# Memory.net
KiCad netlist of a schematic drawn in Altium Designer
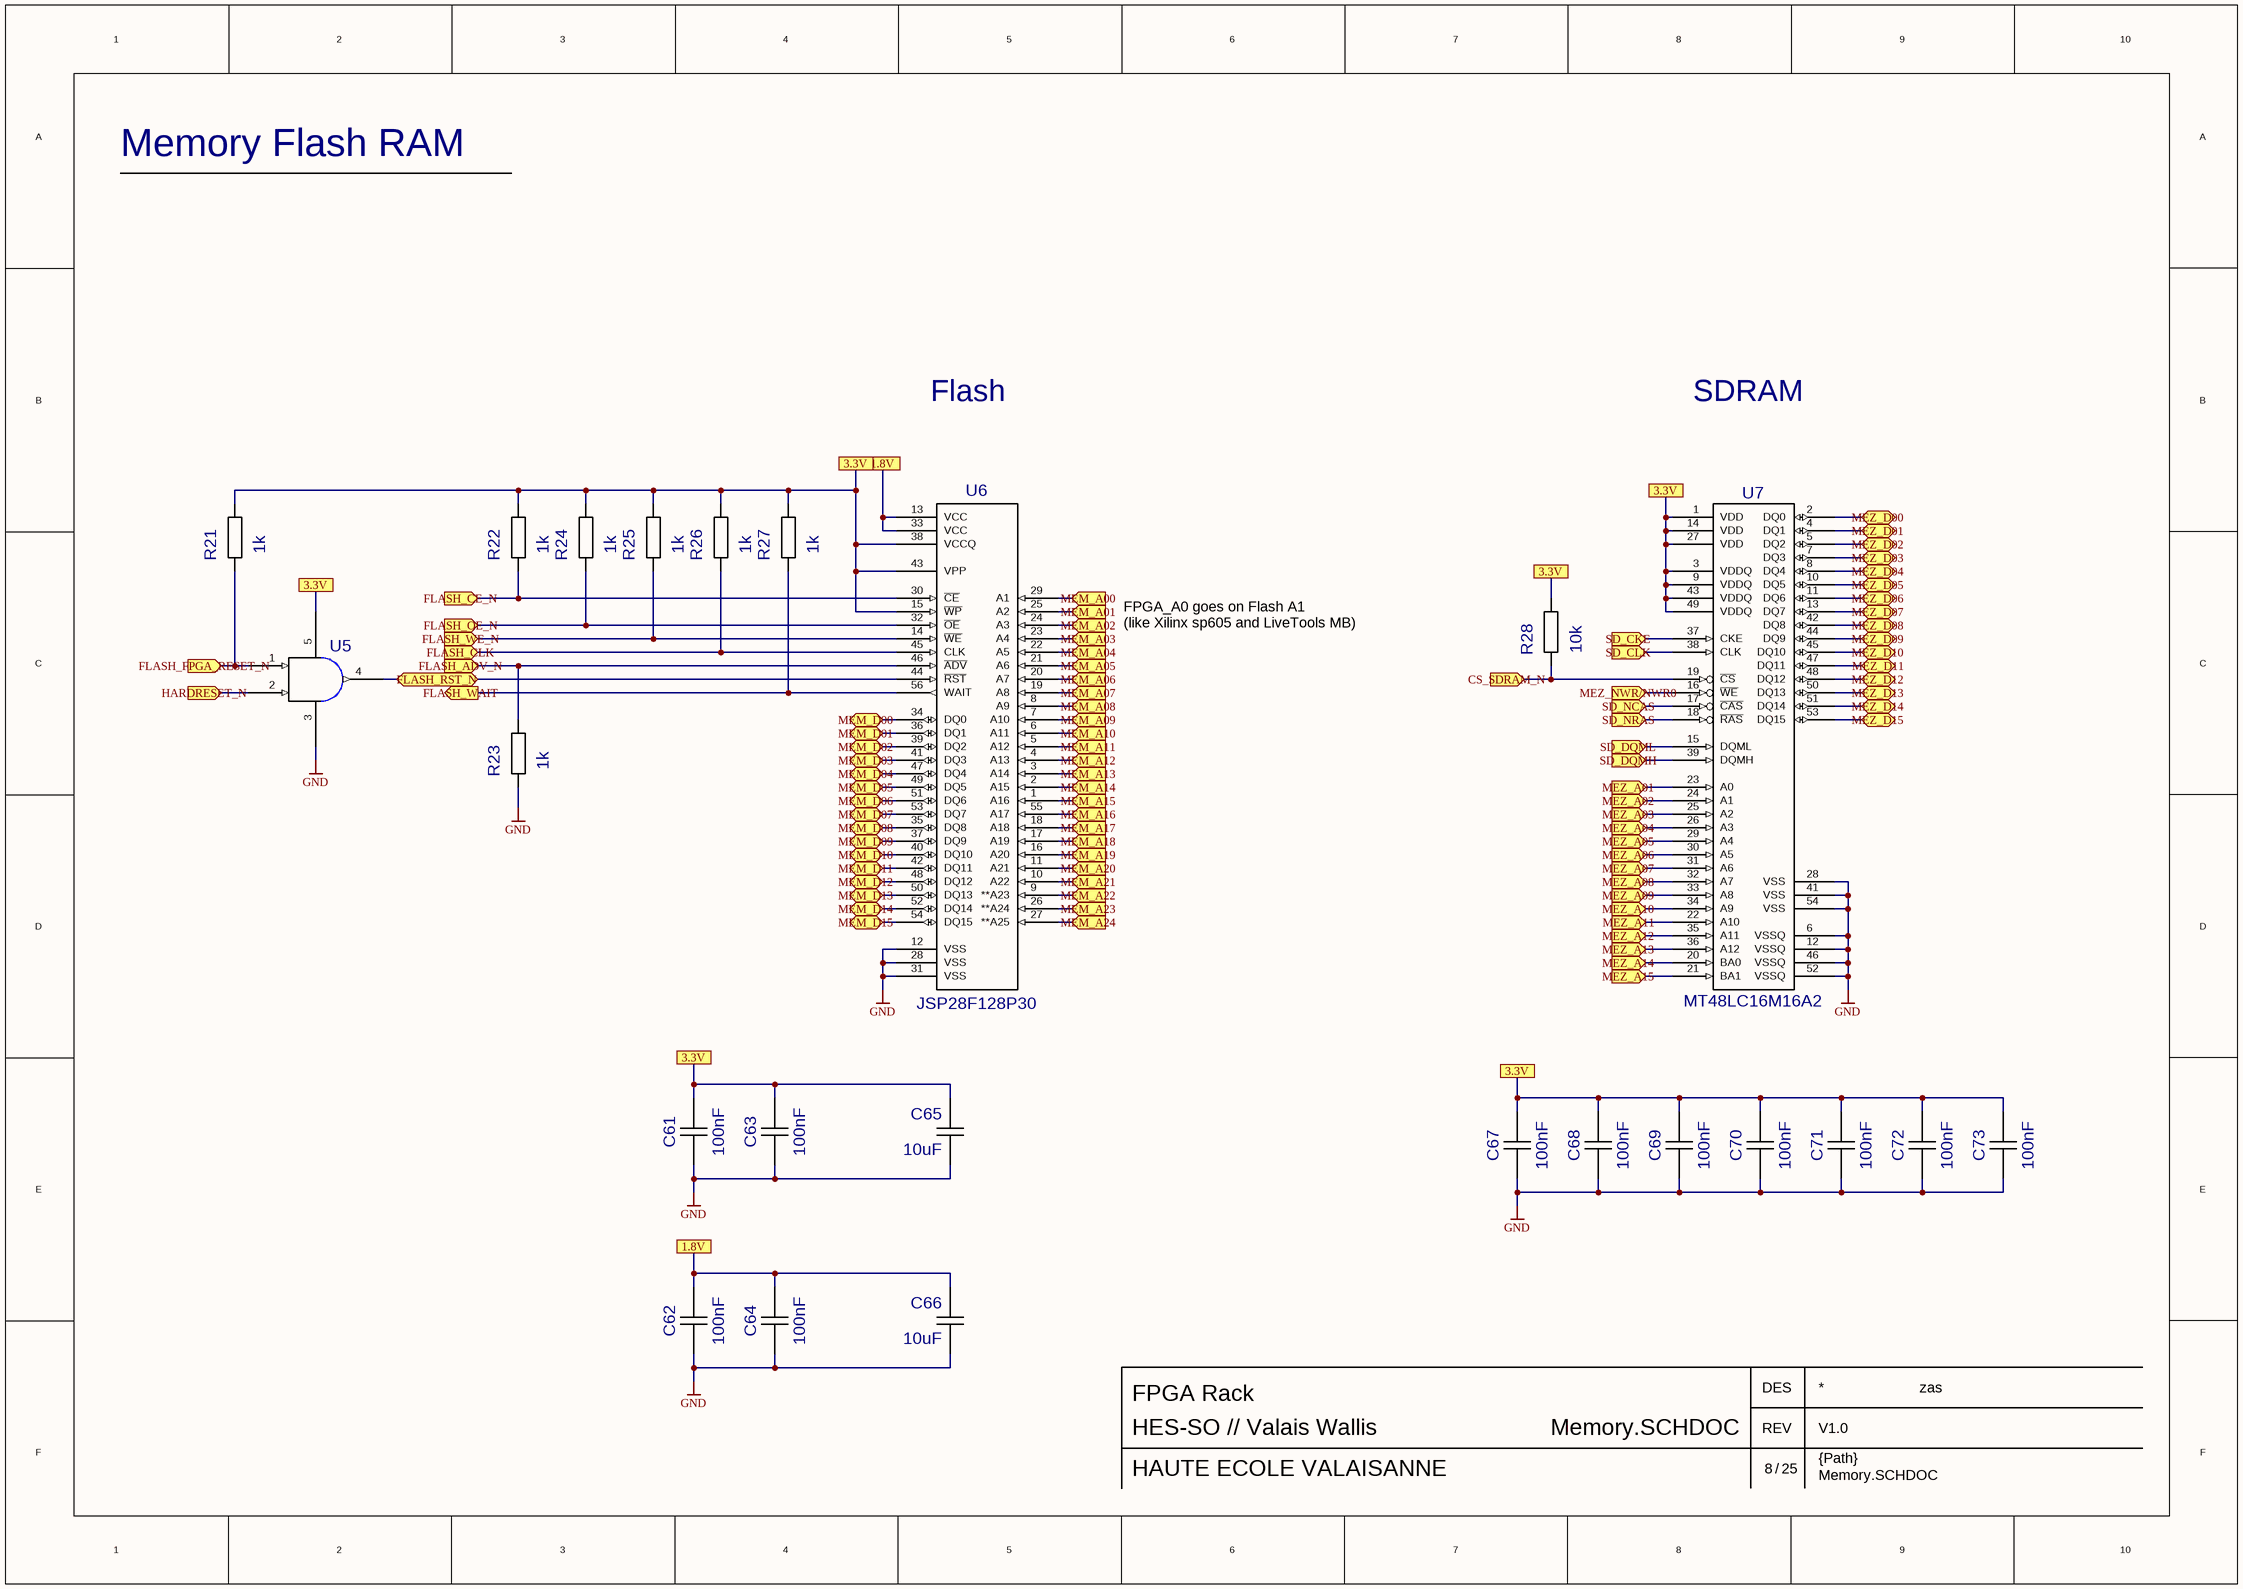
[diagram p0: Memory.SCHDOC]

(export (version "E")
  (design (tool "Eeschema 10.0.6"))
  (components
    (comp (ref "C61")
      (value "100nF")
      (footprint "CC0805-MM")
      (description "Capacitor")
      (fields (field (name "Comment") "CAPS0805-MM"))
      (libsource (lib "*") (part "CAPS0805-MM"))
    )
    (comp (ref "C62")
      (value "100nF")
      (footprint "CC0805-MM")
      (description "Capacitor")
      (fields (field (name "Comment") "CAPS0805-MM"))
      (libsource (lib "*") (part "CAPS0805-MM"))
    )
    (comp (ref "C63")
      (value "100nF")
      (footprint "CC0805-MM")
      (description "Capacitor")
      (fields (field (name "Comment") "CAPS0805-MM"))
      (libsource (lib "*") (part "CAPS0805-MM"))
    )
    (comp (ref "C64")
      (value "100nF")
      (footprint "CC0805-MM")
      (description "Capacitor")
      (fields (field (name "Comment") "CAPS0805-MM"))
      (libsource (lib "*") (part "CAPS0805-MM"))
    )
    (comp (ref "C65")
      (value "10uF")
      (footprint "CC0805-MM")
      (description "Capacitor")
      (fields (field (name "Comment") "CAPS0805-MM"))
      (libsource (lib "*") (part "CAPS0805-MM"))
    )
    (comp (ref "C66")
      (value "10uF")
      (footprint "CC0805-MM")
      (description "Capacitor")
      (fields (field (name "Comment") "CAPS0805-MM"))
      (libsource (lib "*") (part "CAPS0805-MM"))
    )
    (comp (ref "C67")
      (value "100nF")
      (footprint "CC0805-MM")
      (description "Capacitor")
      (fields (field (name "Comment") "CAPS0805-MM"))
      (libsource (lib "*") (part "CAPS0805-MM"))
    )
    (comp (ref "C68")
      (value "100nF")
      (footprint "CC0805-MM")
      (description "Capacitor")
      (fields (field (name "Comment") "CAPS0805-MM"))
      (libsource (lib "*") (part "CAPS0805-MM"))
    )
    (comp (ref "C69")
      (value "100nF")
      (footprint "CC0805-MM")
      (description "Capacitor")
      (fields (field (name "Comment") "CAPS0805-MM"))
      (libsource (lib "*") (part "CAPS0805-MM"))
    )
    (comp (ref "C70")
      (value "100nF")
      (footprint "CC0805-MM")
      (description "Capacitor")
      (fields (field (name "Comment") "CAPS0805-MM"))
      (libsource (lib "*") (part "CAPS0805-MM"))
    )
    (comp (ref "C71")
      (value "100nF")
      (footprint "CC0805-MM")
      (description "Capacitor")
      (fields (field (name "Comment") "CAPS0805-MM"))
      (libsource (lib "*") (part "CAPS0805-MM"))
    )
    (comp (ref "C72")
      (value "100nF")
      (footprint "CC0805-MM")
      (description "Capacitor")
      (fields (field (name "Comment") "CAPS0805-MM"))
      (libsource (lib "*") (part "CAPS0805-MM"))
    )
    (comp (ref "C73")
      (value "100nF")
      (footprint "CC0805-MM")
      (description "Capacitor")
      (fields (field (name "Comment") "CAPS0805-MM"))
      (libsource (lib "*") (part "CAPS0805-MM"))
    )
    (comp (ref "R21")
      (value "1k")
      (footprint "RC0805-MM")
      (description "RS0805-MM")
      (libsource (lib "*") (part "RS0805-MM"))
    )
    (comp (ref "R22")
      (value "1k")
      (footprint "RC0805-MM")
      (description "RS0805-MM")
      (libsource (lib "*") (part "RS0805-MM"))
    )
    (comp (ref "R23")
      (value "1k")
      (footprint "RC0805-MM")
      (description "RS0805-MM")
      (libsource (lib "*") (part "RS0805-MM"))
    )
    (comp (ref "R24")
      (value "1k")
      (footprint "RC0805-MM")
      (description "RS0805-MM")
      (libsource (lib "*") (part "RS0805-MM"))
    )
    (comp (ref "R25")
      (value "1k")
      (footprint "RC0805-MM")
      (description "RS0805-MM")
      (libsource (lib "*") (part "RS0805-MM"))
    )
    (comp (ref "R26")
      (value "1k")
      (footprint "RC0805-MM")
      (description "RS0805-MM")
      (libsource (lib "*") (part "RS0805-MM"))
    )
    (comp (ref "R27")
      (value "1k")
      (footprint "RC0805-MM")
      (description "RS0805-MM")
      (libsource (lib "*") (part "RS0805-MM"))
    )
    (comp (ref "R28")
      (value "10k")
      (footprint "RC0805-MM")
      (description "RS0805-MM")
      (libsource (lib "*") (part "RS0805-MM"))
    )
    (comp (ref "U5")
      (value "NC7SZ08P5")
      (footprint "SC70-5")
      (description "HS Inverter - Fairchild")
      (libsource (lib "*") (part "NC7SZ08P5"))
    )
    (comp (ref "U6")
      (value "JSP28F128P30")
      (footprint "TSOP56")
      (description "SDRAM 64Mb x 16 - Micron")
      (fields (field (name "Comment") "JS28F512P30"))
      (libsource (lib "*") (part "JS28F512P30"))
    )
    (comp (ref "U7")
      (value "MT48LC16M16A2")
      (footprint "TSOP54")
      (description "SDRAM 64Mb x 16 - Micron")
      (libsource (lib "*") (part "MT48LC16M16A2"))
    )
  )
  (nets
    (net (code "3") (name "/CS_SDRAM_N") (class "Default")
      (node (ref "R28") (pin "1") (pinfunction "1_1") (pintype "passive"))
      (node (ref "U7") (pin "19") (pinfunction "~{CS}_19") (pintype "input"))
    )
    (net (code "4") (name "/FLASH_ADV_N") (class "Default")
      (node (ref "R23") (pin "2") (pinfunction "2_2") (pintype "passive"))
      (node (ref "U6") (pin "46") (pinfunction "~{ADV}_46") (pintype "input"))
    )
    (net (code "5") (name "/FLASH_CE_N") (class "Default")
      (node (ref "R22") (pin "1") (pinfunction "1_1") (pintype "passive"))
      (node (ref "U6") (pin "30") (pinfunction "~{CE}_30") (pintype "input"))
    )
    (net (code "6") (name "/FLASH_CLK") (class "Default")
      (node (ref "R26") (pin "1") (pinfunction "1_1") (pintype "passive"))
      (node (ref "U6") (pin "45") (pinfunction "CLK_45") (pintype "input"))
    )
    (net (code "7") (name "/FLASH_FPGA_RESET_N") (class "Default")
      (node (ref "R21") (pin "1") (pinfunction "1_1") (pintype "passive"))
      (node (ref "U5") (pin "1") (pinfunction "A_1") (pintype "input"))
    )
    (net (code "8") (name "/FLASH_OE_N") (class "Default")
      (node (ref "R24") (pin "1") (pinfunction "1_1") (pintype "passive"))
      (node (ref "U6") (pin "32") (pinfunction "~{OE}_32") (pintype "input"))
    )
    (net (code "9") (name "/FLASH_RST_N") (class "Default")
      (node (ref "U5") (pin "4") (pinfunction "Y_4") (pintype "output"))
      (node (ref "U6") (pin "44") (pinfunction "~{RST}_44") (pintype "input"))
    )
    (net (code "10") (name "/FLASH_WAIT") (class "Default")
      (node (ref "R27") (pin "1") (pinfunction "1_1") (pintype "passive"))
      (node (ref "U6") (pin "56") (pinfunction "WAIT_56") (pintype "output"))
    )
    (net (code "11") (name "/FLASH_WE_N") (class "Default")
      (node (ref "R25") (pin "1") (pinfunction "1_1") (pintype "passive"))
      (node (ref "U6") (pin "14") (pinfunction "~{WE}_14") (pintype "input"))
    )
    (net (code "12") (name "/HARDRESET_N") (class "Default")
      (node (ref "U5") (pin "2") (pinfunction "B_2") (pintype "input"))
    )
    (net (code "13") (name "/MEM_A00") (class "Default")
      (node (ref "U6") (pin "29") (pinfunction "A1_29") (pintype "input"))
    )
    (net (code "14") (name "/MEM_A01") (class "Default")
      (node (ref "U6") (pin "25") (pinfunction "A2_25") (pintype "input"))
    )
    (net (code "15") (name "/MEM_A02") (class "Default")
      (node (ref "U6") (pin "24") (pinfunction "A3_24") (pintype "input"))
    )
    (net (code "16") (name "/MEM_A03") (class "Default")
      (node (ref "U6") (pin "23") (pinfunction "A4_23") (pintype "input"))
    )
    (net (code "17") (name "/MEM_A04") (class "Default")
      (node (ref "U6") (pin "22") (pinfunction "A5_22") (pintype "input"))
    )
    (net (code "18") (name "/MEM_A05") (class "Default")
      (node (ref "U6") (pin "21") (pinfunction "A6_21") (pintype "input"))
    )
    (net (code "19") (name "/MEM_A06") (class "Default")
      (node (ref "U6") (pin "20") (pinfunction "A7_20") (pintype "input"))
    )
    (net (code "20") (name "/MEM_A07") (class "Default")
      (node (ref "U6") (pin "19") (pinfunction "A8_19") (pintype "input"))
    )
    (net (code "21") (name "/MEM_A08") (class "Default")
      (node (ref "U6") (pin "8") (pinfunction "A9_8") (pintype "input"))
    )
    (net (code "22") (name "/MEM_A09") (class "Default")
      (node (ref "U6") (pin "7") (pinfunction "A10_7") (pintype "input"))
    )
    (net (code "23") (name "/MEM_A10") (class "Default")
      (node (ref "U6") (pin "6") (pinfunction "A11_6") (pintype "input"))
    )
    (net (code "24") (name "/MEM_A11") (class "Default")
      (node (ref "U6") (pin "5") (pinfunction "A12_5") (pintype "input"))
    )
    (net (code "25") (name "/MEM_A12") (class "Default")
      (node (ref "U6") (pin "4") (pinfunction "A13_4") (pintype "input"))
    )
    (net (code "26") (name "/MEM_A13") (class "Default")
      (node (ref "U6") (pin "3") (pinfunction "A14_3") (pintype "input"))
    )
    (net (code "27") (name "/MEM_A14") (class "Default")
      (node (ref "U6") (pin "2") (pinfunction "A15_2") (pintype "input"))
    )
    (net (code "28") (name "/MEM_A15") (class "Default")
      (node (ref "U6") (pin "1") (pinfunction "A16_1") (pintype "input"))
    )
    (net (code "29") (name "/MEM_A16") (class "Default")
      (node (ref "U6") (pin "55") (pinfunction "A17_55") (pintype "input"))
    )
    (net (code "30") (name "/MEM_A17") (class "Default")
      (node (ref "U6") (pin "18") (pinfunction "A18_18") (pintype "input"))
    )
    (net (code "31") (name "/MEM_A18") (class "Default")
      (node (ref "U6") (pin "17") (pinfunction "A19_17") (pintype "input"))
    )
    (net (code "32") (name "/MEM_A19") (class "Default")
      (node (ref "U6") (pin "16") (pinfunction "A20_16") (pintype "input"))
    )
    (net (code "33") (name "/MEM_A20") (class "Default")
      (node (ref "U6") (pin "11") (pinfunction "A21_11") (pintype "input"))
    )
    (net (code "34") (name "/MEM_A21") (class "Default")
      (node (ref "U6") (pin "10") (pinfunction "A22_10") (pintype "input"))
    )
    (net (code "35") (name "/MEM_A22") (class "Default")
      (node (ref "U6") (pin "9") (pinfunction "**A23_9") (pintype "input"))
    )
    (net (code "36") (name "/MEM_A23") (class "Default")
      (node (ref "U6") (pin "26") (pinfunction "**A24_26") (pintype "input"))
    )
    (net (code "37") (name "/MEM_A24") (class "Default")
      (node (ref "U6") (pin "27") (pinfunction "**A25_27") (pintype "input"))
    )
    (net (code "38") (name "/MEM_D00") (class "Default")
      (node (ref "U6") (pin "34") (pinfunction "DQ0_34") (pintype "bidirectional"))
    )
    (net (code "39") (name "/MEM_D01") (class "Default")
      (node (ref "U6") (pin "36") (pinfunction "DQ1_36") (pintype "bidirectional"))
    )
    (net (code "40") (name "/MEM_D02") (class "Default")
      (node (ref "U6") (pin "39") (pinfunction "DQ2_39") (pintype "bidirectional"))
    )
    (net (code "41") (name "/MEM_D03") (class "Default")
      (node (ref "U6") (pin "41") (pinfunction "DQ3_41") (pintype "bidirectional"))
    )
    (net (code "42") (name "/MEM_D04") (class "Default")
      (node (ref "U6") (pin "47") (pinfunction "DQ4_47") (pintype "bidirectional"))
    )
    (net (code "43") (name "/MEM_D05") (class "Default")
      (node (ref "U6") (pin "49") (pinfunction "DQ5_49") (pintype "bidirectional"))
    )
    (net (code "44") (name "/MEM_D06") (class "Default")
      (node (ref "U6") (pin "51") (pinfunction "DQ6_51") (pintype "bidirectional"))
    )
    (net (code "45") (name "/MEM_D07") (class "Default")
      (node (ref "U6") (pin "53") (pinfunction "DQ7_53") (pintype "bidirectional"))
    )
    (net (code "46") (name "/MEM_D08") (class "Default")
      (node (ref "U6") (pin "35") (pinfunction "DQ8_35") (pintype "bidirectional"))
    )
    (net (code "47") (name "/MEM_D09") (class "Default")
      (node (ref "U6") (pin "37") (pinfunction "DQ9_37") (pintype "bidirectional"))
    )
    (net (code "48") (name "/MEM_D10") (class "Default")
      (node (ref "U6") (pin "40") (pinfunction "DQ10_40") (pintype "bidirectional"))
    )
    (net (code "49") (name "/MEM_D11") (class "Default")
      (node (ref "U6") (pin "42") (pinfunction "DQ11_42") (pintype "bidirectional"))
    )
    (net (code "50") (name "/MEM_D12") (class "Default")
      (node (ref "U6") (pin "48") (pinfunction "DQ12_48") (pintype "bidirectional"))
    )
    (net (code "51") (name "/MEM_D13") (class "Default")
      (node (ref "U6") (pin "50") (pinfunction "DQ13_50") (pintype "bidirectional"))
    )
    (net (code "52") (name "/MEM_D14") (class "Default")
      (node (ref "U6") (pin "52") (pinfunction "DQ14_52") (pintype "bidirectional"))
    )
    (net (code "53") (name "/MEM_D15") (class "Default")
      (node (ref "U6") (pin "54") (pinfunction "DQ15_54") (pintype "bidirectional"))
    )
    (net (code "54") (name "/MEZ_A01") (class "Default")
      (node (ref "U7") (pin "23") (pinfunction "A0_23") (pintype "input"))
    )
    (net (code "55") (name "/MEZ_A02") (class "Default")
      (node (ref "U7") (pin "24") (pinfunction "A1_24") (pintype "input"))
    )
    (net (code "56") (name "/MEZ_A03") (class "Default")
      (node (ref "U7") (pin "25") (pinfunction "A2_25") (pintype "input"))
    )
    (net (code "57") (name "/MEZ_A04") (class "Default")
      (node (ref "U7") (pin "26") (pinfunction "A3_26") (pintype "input"))
    )
    (net (code "58") (name "/MEZ_A05") (class "Default")
      (node (ref "U7") (pin "29") (pinfunction "A4_29") (pintype "input"))
    )
    (net (code "59") (name "/MEZ_A06") (class "Default")
      (node (ref "U7") (pin "30") (pinfunction "A5_30") (pintype "input"))
    )
    (net (code "60") (name "/MEZ_A07") (class "Default")
      (node (ref "U7") (pin "31") (pinfunction "A6_31") (pintype "input"))
    )
    (net (code "61") (name "/MEZ_A08") (class "Default")
      (node (ref "U7") (pin "32") (pinfunction "A7_32") (pintype "input"))
    )
    (net (code "62") (name "/MEZ_A09") (class "Default")
      (node (ref "U7") (pin "33") (pinfunction "A8_33") (pintype "input"))
    )
    (net (code "63") (name "/MEZ_A10") (class "Default")
      (node (ref "U7") (pin "34") (pinfunction "A9_34") (pintype "input"))
    )
    (net (code "64") (name "/MEZ_A11") (class "Default")
      (node (ref "U7") (pin "22") (pinfunction "A10_22") (pintype "input"))
    )
    (net (code "65") (name "/MEZ_A12") (class "Default")
      (node (ref "U7") (pin "35") (pinfunction "A11_35") (pintype "input"))
    )
    (net (code "66") (name "/MEZ_A13") (class "Default")
      (node (ref "U7") (pin "36") (pinfunction "A12_36") (pintype "input"))
    )
    (net (code "67") (name "/MEZ_A14") (class "Default")
      (node (ref "U7") (pin "20") (pinfunction "BA0_20") (pintype "input"))
    )
    (net (code "68") (name "/MEZ_A15") (class "Default")
      (node (ref "U7") (pin "21") (pinfunction "BA1_21") (pintype "input"))
    )
    (net (code "69") (name "/MEZ_D00") (class "Default")
      (node (ref "U7") (pin "2") (pinfunction "DQ0_2") (pintype "bidirectional"))
    )
    (net (code "70") (name "/MEZ_D01") (class "Default")
      (node (ref "U7") (pin "4") (pinfunction "DQ1_4") (pintype "bidirectional"))
    )
    (net (code "71") (name "/MEZ_D02") (class "Default")
      (node (ref "U7") (pin "5") (pinfunction "DQ2_5") (pintype "bidirectional"))
    )
    (net (code "72") (name "/MEZ_D03") (class "Default")
      (node (ref "U7") (pin "7") (pinfunction "DQ3_7") (pintype "bidirectional"))
    )
    (net (code "73") (name "/MEZ_D04") (class "Default")
      (node (ref "U7") (pin "8") (pinfunction "DQ4_8") (pintype "bidirectional"))
    )
    (net (code "74") (name "/MEZ_D05") (class "Default")
      (node (ref "U7") (pin "10") (pinfunction "DQ5_10") (pintype "bidirectional"))
    )
    (net (code "75") (name "/MEZ_D06") (class "Default")
      (node (ref "U7") (pin "11") (pinfunction "DQ6_11") (pintype "bidirectional"))
    )
    (net (code "76") (name "/MEZ_D07") (class "Default")
      (node (ref "U7") (pin "13") (pinfunction "DQ7_13") (pintype "bidirectional"))
    )
    (net (code "77") (name "/MEZ_D08") (class "Default")
      (node (ref "U7") (pin "42") (pinfunction "DQ8_42") (pintype "bidirectional"))
    )
    (net (code "78") (name "/MEZ_D09") (class "Default")
      (node (ref "U7") (pin "44") (pinfunction "DQ9_44") (pintype "bidirectional"))
    )
    (net (code "79") (name "/MEZ_D10") (class "Default")
      (node (ref "U7") (pin "45") (pinfunction "DQ10_45") (pintype "bidirectional"))
    )
    (net (code "80") (name "/MEZ_D11") (class "Default")
      (node (ref "U7") (pin "47") (pinfunction "DQ11_47") (pintype "bidirectional"))
    )
    (net (code "81") (name "/MEZ_D12") (class "Default")
      (node (ref "U7") (pin "48") (pinfunction "DQ12_48") (pintype "bidirectional"))
    )
    (net (code "82") (name "/MEZ_D13") (class "Default")
      (node (ref "U7") (pin "50") (pinfunction "DQ13_50") (pintype "bidirectional"))
    )
    (net (code "83") (name "/MEZ_D14") (class "Default")
      (node (ref "U7") (pin "51") (pinfunction "DQ14_51") (pintype "bidirectional"))
    )
    (net (code "84") (name "/MEZ_D15") (class "Default")
      (node (ref "U7") (pin "53") (pinfunction "DQ15_53") (pintype "bidirectional"))
    )
    (net (code "85") (name "/MEZ_NWR{slash}NWR0") (class "Default")
      (node (ref "U7") (pin "16") (pinfunction "~{WE}_16") (pintype "input"))
    )
    (net (code "86") (name "/SD_CKE") (class "Default")
      (node (ref "U7") (pin "37") (pinfunction "CKE_37") (pintype "input"))
    )
    (net (code "87") (name "/SD_CLK") (class "Default")
      (node (ref "U7") (pin "38") (pinfunction "CLK_38") (pintype "input"))
    )
    (net (code "88") (name "/SD_DQMH") (class "Default")
      (node (ref "U7") (pin "39") (pinfunction "DQMH_39") (pintype "input"))
    )
    (net (code "89") (name "/SD_DQML") (class "Default")
      (node (ref "U7") (pin "15") (pinfunction "DQML_15") (pintype "input"))
    )
    (net (code "90") (name "/SD_NCAS") (class "Default")
      (node (ref "U7") (pin "17") (pinfunction "~{CAS}_17") (pintype "input"))
    )
    (net (code "91") (name "/SD_NRAS") (class "Default")
      (node (ref "U7") (pin "18") (pinfunction "~{RAS}_18") (pintype "input"))
    )
    (net (code "92") (name "GND") (class "Default")
      (node (ref "C61") (pin "1") (pinfunction "1_1") (pintype "passive"))
      (node (ref "C62") (pin "1") (pinfunction "1_1") (pintype "passive"))
      (node (ref "C63") (pin "1") (pinfunction "1_1") (pintype "passive"))
      (node (ref "C64") (pin "1") (pinfunction "1_1") (pintype "passive"))
      (node (ref "C65") (pin "1") (pinfunction "1_1") (pintype "passive"))
      (node (ref "C66") (pin "1") (pinfunction "1_1") (pintype "passive"))
      (node (ref "C67") (pin "1") (pinfunction "1_1") (pintype "passive"))
      (node (ref "C68") (pin "1") (pinfunction "1_1") (pintype "passive"))
      (node (ref "C69") (pin "1") (pinfunction "1_1") (pintype "passive"))
      (node (ref "C70") (pin "1") (pinfunction "1_1") (pintype "passive"))
      (node (ref "C71") (pin "1") (pinfunction "1_1") (pintype "passive"))
      (node (ref "C72") (pin "1") (pinfunction "1_1") (pintype "passive"))
      (node (ref "C73") (pin "1") (pinfunction "1_1") (pintype "passive"))
      (node (ref "R23") (pin "1") (pinfunction "1_1") (pintype "passive"))
      (node (ref "U5") (pin "3") (pinfunction "GND_3") (pintype "power_in"))
      (node (ref "U6") (pin "12") (pinfunction "VSS_12") (pintype "power_in"))
      (node (ref "U6") (pin "28") (pinfunction "VSS_28") (pintype "power_in"))
      (node (ref "U6") (pin "31") (pinfunction "VSS_31") (pintype "power_in"))
      (node (ref "U7") (pin "12") (pinfunction "VSSQ_12") (pintype "power_in"))
      (node (ref "U7") (pin "28") (pinfunction "VSS_28") (pintype "power_in"))
      (node (ref "U7") (pin "41") (pinfunction "VSS_41") (pintype "power_in"))
      (node (ref "U7") (pin "46") (pinfunction "VSSQ_46") (pintype "power_in"))
      (node (ref "U7") (pin "52") (pinfunction "VSSQ_52") (pintype "power_in"))
      (node (ref "U7") (pin "54") (pinfunction "VSS_54") (pintype "power_in"))
      (node (ref "U7") (pin "6") (pinfunction "VSSQ_6") (pintype "power_in"))
    )
    (net (code "93") (name "Net-(C61-Pad2)") (class "Default")
      (node (ref "C61") (pin "2") (pinfunction "2_2") (pintype "passive"))
      (node (ref "C63") (pin "2") (pinfunction "2_2") (pintype "passive"))
      (node (ref "C65") (pin "2") (pinfunction "2_2") (pintype "passive"))
    )
    (net (code "94") (name "Net-(C62-Pad2)") (class "Default")
      (node (ref "C62") (pin "2") (pinfunction "2_2") (pintype "passive"))
      (node (ref "C64") (pin "2") (pinfunction "2_2") (pintype "passive"))
      (node (ref "C66") (pin "2") (pinfunction "2_2") (pintype "passive"))
    )
    (net (code "95") (name "Net-(C67-Pad2)") (class "Default")
      (node (ref "C67") (pin "2") (pinfunction "2_2") (pintype "passive"))
      (node (ref "C68") (pin "2") (pinfunction "2_2") (pintype "passive"))
      (node (ref "C69") (pin "2") (pinfunction "2_2") (pintype "passive"))
      (node (ref "C70") (pin "2") (pinfunction "2_2") (pintype "passive"))
      (node (ref "C71") (pin "2") (pinfunction "2_2") (pintype "passive"))
      (node (ref "C72") (pin "2") (pinfunction "2_2") (pintype "passive"))
      (node (ref "C73") (pin "2") (pinfunction "2_2") (pintype "passive"))
    )
    (net (code "96") (name "Net-(U6-VCC-Pad13)") (class "Default")
      (node (ref "U6") (pin "13") (pinfunction "VCC_13") (pintype "power_in"))
      (node (ref "U6") (pin "33") (pinfunction "VCC_33") (pintype "power_in"))
    )
    (net (code "97") (name "Net-(U6-VCCQ)") (class "Default")
      (node (ref "R21") (pin "2") (pinfunction "2_2") (pintype "passive"))
      (node (ref "R22") (pin "2") (pinfunction "2_2") (pintype "passive"))
      (node (ref "R24") (pin "2") (pinfunction "2_2") (pintype "passive"))
      (node (ref "R25") (pin "2") (pinfunction "2_2") (pintype "passive"))
      (node (ref "R26") (pin "2") (pinfunction "2_2") (pintype "passive"))
      (node (ref "R27") (pin "2") (pinfunction "2_2") (pintype "passive"))
      (node (ref "U6") (pin "15") (pinfunction "~{WP}_15") (pintype "input"))
      (node (ref "U6") (pin "38") (pinfunction "VCCQ_38") (pintype "power_in"))
      (node (ref "U6") (pin "43") (pinfunction "VPP_43") (pintype "power_in"))
    )
    (net (code "98") (name "Net-(U7-VDD-Pad1)") (class "Default")
      (node (ref "U7") (pin "1") (pinfunction "VDD_1") (pintype "power_in"))
      (node (ref "U7") (pin "14") (pinfunction "VDD_14") (pintype "power_in"))
      (node (ref "U7") (pin "27") (pinfunction "VDD_27") (pintype "power_in"))
      (node (ref "U7") (pin "3") (pinfunction "VDDQ_3") (pintype "power_in"))
      (node (ref "U7") (pin "43") (pinfunction "VDDQ_43") (pintype "power_in"))
      (node (ref "U7") (pin "49") (pinfunction "VDDQ_49") (pintype "power_in"))
      (node (ref "U7") (pin "9") (pinfunction "VDDQ_9") (pintype "power_in"))
    )
    (net (code "99") (name "unconnected-(R28-Pad2)") (class "Default")
      (node (ref "R28") (pin "2") (pinfunction "2_2") (pintype "passive"))
    )
    (net (code "100") (name "unconnected-(U5-VCC-Pad5)") (class "Default")
      (node (ref "U5") (pin "5") (pinfunction "VCC_5") (pintype "power_in"))
    )
    (net (code "101") (name "unconnected-(U7-NC-Pad40)") (class "Default")
      (node (ref "U7") (pin "40") (pinfunction "NC_40") (pintype "passive"))
    )
  )
)
